# ace128_pcf8574_smd_v2.net
KiCad netlist of a schematic drawn in EAGLE
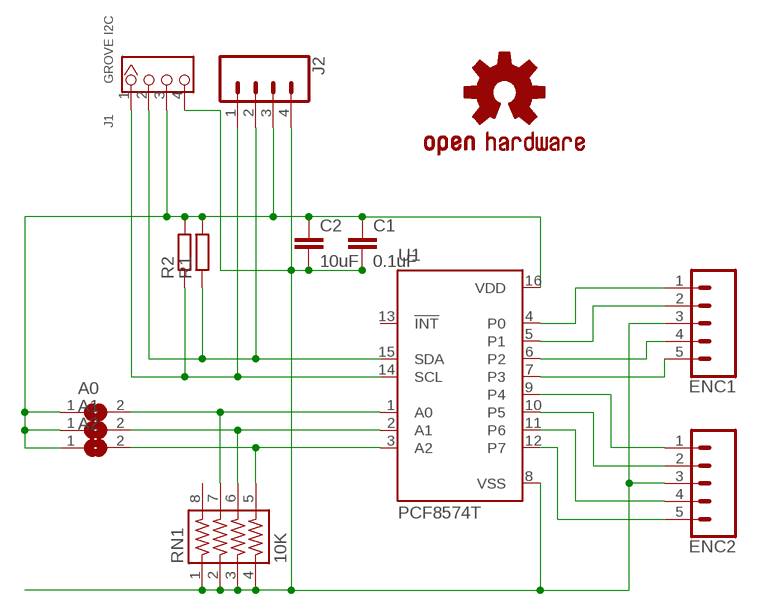
[diagram p0: schematic, sheet 1]

(export (version "E")
  (design (tool "Eeschema 10.0.6"))
  (components
    (comp (ref "A0") (value "SJ") (footprint "eagle-import:SJ") (libsource (lib "eagle-import") (part "SJ")))
    (comp (ref "A1") (value "SJ") (footprint "eagle-import:SJ") (libsource (lib "eagle-import") (part "SJ")))
    (comp (ref "A2") (value "SJ") (footprint "eagle-import:SJ") (libsource (lib "eagle-import") (part "SJ")))
    (comp (ref "C1")
      (value "0.1uF")
      (footprint "eagle-import:C0603")
      (libsource (lib "eagle-import") (part "rcl_334_C-EUC0603"))
    )
    (comp (ref "C2")
      (value "10uF")
      (footprint "eagle-import:C0805")
      (libsource (lib "eagle-import") (part "C-EUC0805"))
    )
    (comp (ref "ENC1")
      (value "CONN_05")
      (footprint "eagle-import:1X05")
      (libsource (lib "eagle-import") (part "CONN_05"))
    )
    (comp (ref "ENC2")
      (value "CONN_05")
      (footprint "eagle-import:1X05")
      (libsource (lib "eagle-import") (part "CONN_05"))
    )
    (comp (ref "J1")
      (value "GROVE I2C")
      (footprint "eagle-import:HW4-2.0")
      (libsource (lib "eagle-import") (part "GROVE-CONNECTOR-DIP(4P-2.0)"))
    )
    (comp (ref "J2")
      (value "CONN_04")
      (footprint "eagle-import:1X04")
      (libsource (lib "eagle-import") (part "CONN_04"))
    )
    (comp (ref "LOGO1")
      (value "OSHW-LOGOS")
      (footprint "eagle-import:OSHW-LOGO-S")
      (libsource (lib "eagle-import") (part "OSHW-LOGOS"))
    )
    (comp (ref "R1")
      (value "R-EU_0207/2V")
      (footprint "eagle-import:0207_2V")
      (libsource (lib "eagle-import") (part "R-EU_0207/2V"))
    )
    (comp (ref "R2")
      (value "R-EU_0207/2V")
      (footprint "eagle-import:0207_2V")
      (libsource (lib "eagle-import") (part "R-EU_0207/2V"))
    )
    (comp (ref "RN1")
      (value "10K")
      (footprint "eagle-import:743-8")
      (libsource (lib "eagle-import") (part "743-8"))
    )
    (comp (ref "U1")
      (value "PCF8574T")
      (footprint "eagle-import:SO16W")
      (fields (field (name "MPN") "PCF8574T/3,512"))
      (libsource (lib "eagle-import") (part "PCF8574T"))
    )
  )
  (nets
    (net (code "1") (name "Net-(U1-A0)") (class "Default")
      (node (ref "A0") (pin "2") (pinfunction "2_2") (pintype "passive"))
      (node (ref "RN1") (pin "7") (pinfunction "7_7") (pintype "passive"))
      (node (ref "U1") (pin "1") (pinfunction "A0_1") (pintype "input"))
    )
    (net (code "2") (name "Net-(U1-A1)") (class "Default")
      (node (ref "A1") (pin "2") (pinfunction "2_2") (pintype "passive"))
      (node (ref "RN1") (pin "6") (pinfunction "6_6") (pintype "passive"))
      (node (ref "U1") (pin "2") (pinfunction "A1_2") (pintype "input"))
    )
    (net (code "3") (name "Net-(U1-A2)") (class "Default")
      (node (ref "A2") (pin "2") (pinfunction "2_2") (pintype "passive"))
      (node (ref "RN1") (pin "5") (pinfunction "5_5") (pintype "passive"))
      (node (ref "U1") (pin "3") (pinfunction "A2_3") (pintype "input"))
    )
    (net (code "4") (name "Net-(U1-P0)") (class "Default")
      (node (ref "ENC1") (pin "1") (pinfunction "1_1") (pintype "passive"))
      (node (ref "U1") (pin "4") (pinfunction "P0_4") (pintype "bidirectional"))
    )
    (net (code "5") (name "Net-(U1-P1)") (class "Default")
      (node (ref "ENC1") (pin "2") (pinfunction "2_2") (pintype "passive"))
      (node (ref "U1") (pin "5") (pinfunction "P1_5") (pintype "bidirectional"))
    )
    (net (code "6") (name "Net-(U1-P2)") (class "Default")
      (node (ref "ENC1") (pin "4") (pinfunction "4_4") (pintype "passive"))
      (node (ref "U1") (pin "6") (pinfunction "P2_6") (pintype "bidirectional"))
    )
    (net (code "7") (name "Net-(U1-P3)") (class "Default")
      (node (ref "ENC1") (pin "5") (pinfunction "5_5") (pintype "passive"))
      (node (ref "U1") (pin "7") (pinfunction "P3_7") (pintype "bidirectional"))
    )
    (net (code "8") (name "Net-(U1-P4)") (class "Default")
      (node (ref "ENC2") (pin "1") (pinfunction "1_1") (pintype "passive"))
      (node (ref "U1") (pin "9") (pinfunction "P4_9") (pintype "bidirectional"))
    )
    (net (code "9") (name "Net-(U1-P5)") (class "Default")
      (node (ref "ENC2") (pin "2") (pinfunction "2_2") (pintype "passive"))
      (node (ref "U1") (pin "10") (pinfunction "P5_10") (pintype "bidirectional"))
    )
    (net (code "10") (name "Net-(U1-P6)") (class "Default")
      (node (ref "ENC2") (pin "4") (pinfunction "4_4") (pintype "passive"))
      (node (ref "U1") (pin "11") (pinfunction "P6_11") (pintype "bidirectional"))
    )
    (net (code "11") (name "Net-(U1-P7)") (class "Default")
      (node (ref "ENC2") (pin "5") (pinfunction "5_5") (pintype "passive"))
      (node (ref "U1") (pin "12") (pinfunction "P7_12") (pintype "bidirectional"))
    )
    (net (code "12") (name "Net-(U1-SCL)") (class "Default")
      (node (ref "J1") (pin "1") (pinfunction "1_1") (pintype "bidirectional"))
      (node (ref "J2") (pin "1") (pinfunction "1_1") (pintype "passive"))
      (node (ref "R2") (pin "1") (pinfunction "1_1") (pintype "passive"))
      (node (ref "U1") (pin "14") (pinfunction "SCL_14") (pintype "input"))
    )
    (net (code "13") (name "Net-(U1-SDA)") (class "Default")
      (node (ref "J1") (pin "2") (pinfunction "2_2") (pintype "bidirectional"))
      (node (ref "J2") (pin "2") (pinfunction "2_2") (pintype "passive"))
      (node (ref "R1") (pin "1") (pinfunction "1_1") (pintype "passive"))
      (node (ref "U1") (pin "15") (pinfunction "SDA_15") (pintype "bidirectional"))
    )
    (net (code "14") (name "Net-(U1-VDD)") (class "Default")
      (node (ref "A0") (pin "1") (pinfunction "1_1") (pintype "passive"))
      (node (ref "A1") (pin "1") (pinfunction "1_1") (pintype "passive"))
      (node (ref "A2") (pin "1") (pinfunction "1_1") (pintype "passive"))
      (node (ref "C1") (pin "1") (pinfunction "1_1") (pintype "passive"))
      (node (ref "C2") (pin "1") (pinfunction "1_1") (pintype "passive"))
      (node (ref "J1") (pin "3") (pinfunction "3_3") (pintype "bidirectional"))
      (node (ref "J2") (pin "3") (pinfunction "3_3") (pintype "passive"))
      (node (ref "R1") (pin "2") (pinfunction "2_2") (pintype "passive"))
      (node (ref "R2") (pin "2") (pinfunction "2_2") (pintype "passive"))
      (node (ref "U1") (pin "16") (pinfunction "VDD_16") (pintype "power_in"))
    )
    (net (code "15") (name "Net-(U1-VSS)") (class "Default")
      (node (ref "C1") (pin "2") (pinfunction "2_2") (pintype "passive"))
      (node (ref "C2") (pin "2") (pinfunction "2_2") (pintype "passive"))
      (node (ref "ENC1") (pin "3") (pinfunction "3_3") (pintype "passive"))
      (node (ref "ENC2") (pin "3") (pinfunction "3_3") (pintype "passive"))
      (node (ref "J1") (pin "4") (pinfunction "4_4") (pintype "bidirectional"))
      (node (ref "J2") (pin "4") (pinfunction "4_4") (pintype "passive"))
      (node (ref "RN1") (pin "1") (pinfunction "1_1") (pintype "passive"))
      (node (ref "RN1") (pin "2") (pinfunction "2_2") (pintype "passive"))
      (node (ref "RN1") (pin "3") (pinfunction "3_3") (pintype "passive"))
      (node (ref "RN1") (pin "4") (pinfunction "4_4") (pintype "passive"))
      (node (ref "U1") (pin "8") (pinfunction "VSS_8") (pintype "power_in"))
    )
    (net (code "16") (name "unconnected-(RN1-Pad8)") (class "Default")
      (node (ref "RN1") (pin "8") (pinfunction "8_8") (pintype "passive"))
    )
    (net (code "17") (name "unconnected-(U1-~{INT}-Pad13)") (class "Default")
      (node (ref "U1") (pin "13") (pinfunction "~{INT}_13") (pintype "output"))
    )
  )
)
